# HeartRateSensor_Eval_Board_-_Si1141.net
KiCad netlist of a schematic drawn in EAGLE
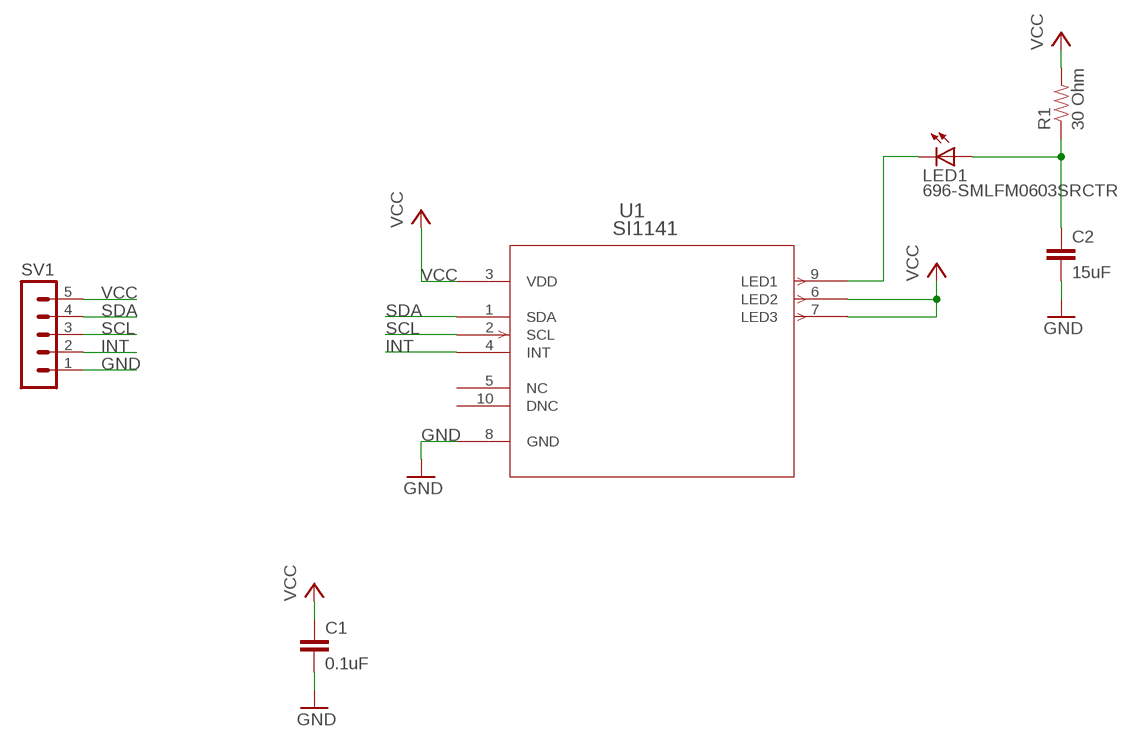
[diagram p0: schematic, sheet 1]

(export (version "E")
  (design (tool "Eeschema 10.0.6"))
  (components
    (comp (ref "C1")
      (value "0.1uF")
      (footprint "eagle-import:0603-CAP")
      (libsource (lib "eagle-import") (part "0.1UF-100V-10%(0603)"))
    )
    (comp (ref "C2")
      (value "15uF")
      (footprint "eagle-import:0603-CAP")
      (libsource (lib "eagle-import") (part "0.1UF-100V-10%(0603)"))
    )
    (comp (ref "LED1")
      (value "696-SMLFM0603SRCTR")
      (footprint "eagle-import:CHIP-LED0603")
      (libsource (lib "eagle-import") (part "LEDCHIP-LED0603"))
    )
    (comp (ref "R1")
      (value "30 Ohm")
      (footprint "eagle-import:0603")
      (libsource (lib "eagle-import") (part "0OHM1/10W5%(0603)"))
    )
    (comp (ref "SV1")
      (value "MA05-1")
      (footprint "eagle-import:MA05-1")
      (libsource (lib "eagle-import") (part "MA05-1"))
    )
    (comp (ref "U1")
      (value "SI1141")
      (footprint "eagle-import:QFN10")
      (libsource (lib "eagle-import") (part "SI1141"))
    )
  )
  (nets
    (net (code "1") (name "/INT") (class "Default")
      (node (ref "SV1") (pin "2") (pinfunction "2_2") (pintype "passive"))
      (node (ref "U1") (pin "4") (pinfunction "INT_4") (pintype "passive"))
    )
    (net (code "2") (name "/SCL") (class "Default")
      (node (ref "SV1") (pin "3") (pinfunction "3_3") (pintype "passive"))
      (node (ref "U1") (pin "2") (pinfunction "SCL_2") (pintype "input"))
    )
    (net (code "3") (name "/SDA") (class "Default")
      (node (ref "SV1") (pin "4") (pinfunction "4_4") (pintype "passive"))
      (node (ref "U1") (pin "1") (pinfunction "SDA_1") (pintype "passive"))
    )
    (net (code "4") (name "GND") (class "Default")
      (node (ref "C1") (pin "2") (pinfunction "2_2") (pintype "passive"))
      (node (ref "C2") (pin "2") (pinfunction "2_2") (pintype "passive"))
      (node (ref "SV1") (pin "1") (pinfunction "1_1") (pintype "passive"))
      (node (ref "U1") (pin "8") (pinfunction "GND_8") (pintype "power_in"))
    )
    (net (code "5") (name "Net-(C2-Pad1)") (class "Default")
      (node (ref "C2") (pin "1") (pinfunction "1_1") (pintype "passive"))
      (node (ref "LED1") (pin "A") (pinfunction "A_A") (pintype "passive"))
      (node (ref "R1") (pin "1") (pinfunction "1_1") (pintype "passive"))
    )
    (net (code "6") (name "Net-(U1-LED1)") (class "Default")
      (node (ref "LED1") (pin "C") (pinfunction "C_C") (pintype "passive"))
      (node (ref "U1") (pin "9") (pinfunction "LED1_9") (pintype "output"))
    )
    (net (code "7") (name "VCC") (class "Default")
      (node (ref "C1") (pin "1") (pinfunction "1_1") (pintype "passive"))
      (node (ref "R1") (pin "2") (pinfunction "2_2") (pintype "passive"))
      (node (ref "SV1") (pin "5") (pinfunction "5_5") (pintype "passive"))
      (node (ref "U1") (pin "3") (pinfunction "VDD_3") (pintype "power_in"))
      (node (ref "U1") (pin "6") (pinfunction "LED2_6") (pintype "output"))
      (node (ref "U1") (pin "7") (pinfunction "LED3_7") (pintype "output"))
    )
    (net (code "8") (name "unconnected-(U1-DNC-Pad10)") (class "Default")
      (node (ref "U1") (pin "10") (pinfunction "DNC_10") (pintype "no_connect"))
    )
    (net (code "9") (name "unconnected-(U1-NC-Pad5)") (class "Default")
      (node (ref "U1") (pin "5") (pinfunction "NC_5") (pintype "no_connect"))
    )
  )
)
